# Led_Strip_5050_Parrallell.net
KiCad netlist of a schematic drawn in Altium Designer
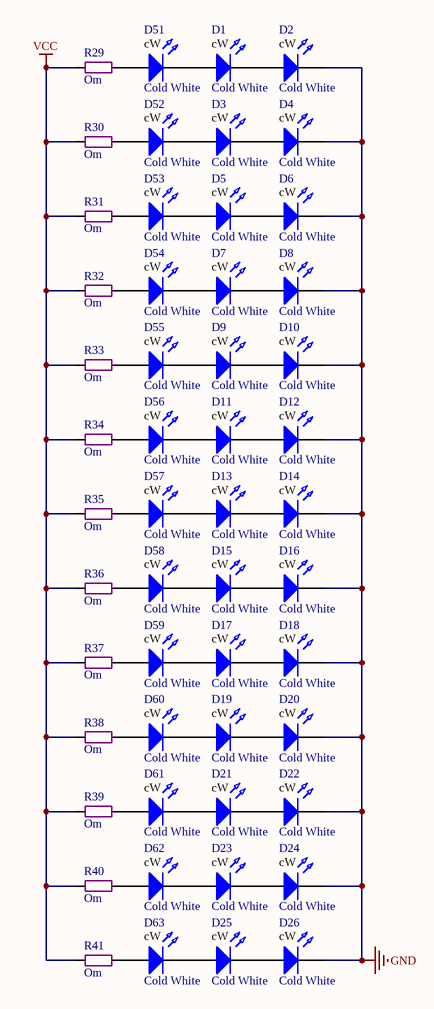
[diagram p0: Led Strip 5050 Parrallell.SchDoc]

(export (version "E")
  (design (tool "Eeschema 10.0.6"))
  (components
    (comp (ref "D1")
      (value "Cold White")
      (footprint "LED:LED SMD 5050 White compact Parrl")
      (description "?3v ?20mA")
      (libsource (lib "LED") (part "Led SMD White Cold"))
    )
    (comp (ref "D2")
      (value "Cold White")
      (footprint "LED:LED SMD 5050 White compact Parrl")
      (description "?3v ?20mA")
      (libsource (lib "LED") (part "Led SMD White Cold"))
    )
    (comp (ref "D3")
      (value "Cold White")
      (footprint "LED:LED SMD 5050 White compact Parrl")
      (description "?3v ?20mA")
      (libsource (lib "LED") (part "Led SMD White Cold"))
    )
    (comp (ref "D4")
      (value "Cold White")
      (footprint "LED:LED SMD 5050 White compact Parrl")
      (description "?3v ?20mA")
      (libsource (lib "LED") (part "Led SMD White Cold"))
    )
    (comp (ref "D5")
      (value "Cold White")
      (footprint "LED:LED SMD 5050 White compact Parrl")
      (description "?3v ?20mA")
      (libsource (lib "LED") (part "Led SMD White Cold"))
    )
    (comp (ref "D6")
      (value "Cold White")
      (footprint "LED:LED SMD 5050 White compact Parrl")
      (description "?3v ?20mA")
      (libsource (lib "LED") (part "Led SMD White Cold"))
    )
    (comp (ref "D7")
      (value "Cold White")
      (footprint "LED:LED SMD 5050 White compact Parrl")
      (description "?3v ?20mA")
      (libsource (lib "LED") (part "Led SMD White Cold"))
    )
    (comp (ref "D8")
      (value "Cold White")
      (footprint "LED:LED SMD 5050 White compact Parrl")
      (description "?3v ?20mA")
      (libsource (lib "LED") (part "Led SMD White Cold"))
    )
    (comp (ref "D9")
      (value "Cold White")
      (footprint "LED:LED SMD 5050 White compact Parrl")
      (description "?3v ?20mA")
      (libsource (lib "LED") (part "Led SMD White Cold"))
    )
    (comp (ref "D10")
      (value "Cold White")
      (footprint "LED:LED SMD 5050 White compact Parrl")
      (description "?3v ?20mA")
      (libsource (lib "LED") (part "Led SMD White Cold"))
    )
    (comp (ref "D11")
      (value "Cold White")
      (footprint "LED:LED SMD 5050 White compact Parrl")
      (description "?3v ?20mA")
      (libsource (lib "LED") (part "Led SMD White Cold"))
    )
    (comp (ref "D12")
      (value "Cold White")
      (footprint "LED:LED SMD 5050 White compact Parrl")
      (description "?3v ?20mA")
      (libsource (lib "LED") (part "Led SMD White Cold"))
    )
    (comp (ref "D13")
      (value "Cold White")
      (footprint "LED:LED SMD 5050 White compact Parrl")
      (description "?3v ?20mA")
      (libsource (lib "LED") (part "Led SMD White Cold"))
    )
    (comp (ref "D14")
      (value "Cold White")
      (footprint "LED:LED SMD 5050 White compact Parrl")
      (description "?3v ?20mA")
      (libsource (lib "LED") (part "Led SMD White Cold"))
    )
    (comp (ref "D15")
      (value "Cold White")
      (footprint "LED:LED SMD 5050 White compact Parrl")
      (description "?3v ?20mA")
      (libsource (lib "LED") (part "Led SMD White Cold"))
    )
    (comp (ref "D16")
      (value "Cold White")
      (footprint "LED:LED SMD 5050 White compact Parrl")
      (description "?3v ?20mA")
      (libsource (lib "LED") (part "Led SMD White Cold"))
    )
    (comp (ref "D17")
      (value "Cold White")
      (footprint "LED:LED SMD 5050 White compact Parrl")
      (description "?3v ?20mA")
      (libsource (lib "LED") (part "Led SMD White Cold"))
    )
    (comp (ref "D18")
      (value "Cold White")
      (footprint "LED:LED SMD 5050 White compact Parrl")
      (description "?3v ?20mA")
      (libsource (lib "LED") (part "Led SMD White Cold"))
    )
    (comp (ref "D19")
      (value "Cold White")
      (footprint "LED:LED SMD 5050 White compact Parrl")
      (description "?3v ?20mA")
      (libsource (lib "LED") (part "Led SMD White Cold"))
    )
    (comp (ref "D20")
      (value "Cold White")
      (footprint "LED:LED SMD 5050 White compact Parrl")
      (description "?3v ?20mA")
      (libsource (lib "LED") (part "Led SMD White Cold"))
    )
    (comp (ref "D21")
      (value "Cold White")
      (footprint "LED:LED SMD 5050 White compact Parrl")
      (description "?3v ?20mA")
      (libsource (lib "LED") (part "Led SMD White Cold"))
    )
    (comp (ref "D22")
      (value "Cold White")
      (footprint "LED:LED SMD 5050 White compact Parrl")
      (description "?3v ?20mA")
      (libsource (lib "LED") (part "Led SMD White Cold"))
    )
    (comp (ref "D23")
      (value "Cold White")
      (footprint "LED:LED SMD 5050 White compact Parrl")
      (description "?3v ?20mA")
      (libsource (lib "LED") (part "Led SMD White Cold"))
    )
    (comp (ref "D24")
      (value "Cold White")
      (footprint "LED:LED SMD 5050 White compact Parrl")
      (description "?3v ?20mA")
      (libsource (lib "LED") (part "Led SMD White Cold"))
    )
    (comp (ref "D25")
      (value "Cold White")
      (footprint "LED:LED SMD 5050 White compact Parrl")
      (description "?3v ?20mA")
      (libsource (lib "LED") (part "Led SMD White Cold"))
    )
    (comp (ref "D26")
      (value "Cold White")
      (footprint "LED:LED SMD 5050 White compact Parrl")
      (description "?3v ?20mA")
      (libsource (lib "LED") (part "Led SMD White Cold"))
    )
    (comp (ref "D51")
      (value "Cold White")
      (footprint "LED:LED SMD 5050 White compact Parrl")
      (description "?3v ?20mA")
      (libsource (lib "LED") (part "Led SMD White Cold"))
    )
    (comp (ref "D52")
      (value "Cold White")
      (footprint "LED:LED SMD 5050 White compact Parrl")
      (description "?3v ?20mA")
      (libsource (lib "LED") (part "Led SMD White Cold"))
    )
    (comp (ref "D53")
      (value "Cold White")
      (footprint "LED:LED SMD 5050 White compact Parrl")
      (description "?3v ?20mA")
      (libsource (lib "LED") (part "Led SMD White Cold"))
    )
    (comp (ref "D54")
      (value "Cold White")
      (footprint "LED:LED SMD 5050 White compact Parrl")
      (description "?3v ?20mA")
      (libsource (lib "LED") (part "Led SMD White Cold"))
    )
    (comp (ref "D55")
      (value "Cold White")
      (footprint "LED:LED SMD 5050 White compact Parrl")
      (description "?3v ?20mA")
      (libsource (lib "LED") (part "Led SMD White Cold"))
    )
    (comp (ref "D56")
      (value "Cold White")
      (footprint "LED:LED SMD 5050 White compact Parrl")
      (description "?3v ?20mA")
      (libsource (lib "LED") (part "Led SMD White Cold"))
    )
    (comp (ref "D57")
      (value "Cold White")
      (footprint "LED:LED SMD 5050 White compact Parrl")
      (description "?3v ?20mA")
      (libsource (lib "LED") (part "Led SMD White Cold"))
    )
    (comp (ref "D58")
      (value "Cold White")
      (footprint "LED:LED SMD 5050 White compact Parrl")
      (description "?3v ?20mA")
      (libsource (lib "LED") (part "Led SMD White Cold"))
    )
    (comp (ref "D59")
      (value "Cold White")
      (footprint "LED:LED SMD 5050 White compact Parrl")
      (description "?3v ?20mA")
      (libsource (lib "LED") (part "Led SMD White Cold"))
    )
    (comp (ref "D60")
      (value "Cold White")
      (footprint "LED:LED SMD 5050 White compact Parrl")
      (description "?3v ?20mA")
      (libsource (lib "LED") (part "Led SMD White Cold"))
    )
    (comp (ref "D61")
      (value "Cold White")
      (footprint "LED:LED SMD 5050 White compact Parrl")
      (description "?3v ?20mA")
      (libsource (lib "LED") (part "Led SMD White Cold"))
    )
    (comp (ref "D62")
      (value "Cold White")
      (footprint "LED:LED SMD 5050 White compact Parrl")
      (description "?3v ?20mA")
      (libsource (lib "LED") (part "Led SMD White Cold"))
    )
    (comp (ref "D63")
      (value "Cold White")
      (footprint "LED:LED SMD 5050 White compact Parrl")
      (description "?3v ?20mA")
      (libsource (lib "LED") (part "Led SMD White Cold"))
    )
    (comp (ref "R29")
      (value "Om")
      (footprint "PassiveComponents:SMD 1206 (3216)")
      (libsource (lib "PassiveComponents") (part "Res SMD 1206"))
    )
    (comp (ref "R30")
      (value "Om")
      (footprint "PassiveComponents:SMD 1206 (3216)")
      (libsource (lib "PassiveComponents") (part "Res SMD 1206"))
    )
    (comp (ref "R31")
      (value "Om")
      (footprint "PassiveComponents:SMD 1206 (3216)")
      (libsource (lib "PassiveComponents") (part "Res SMD 1206"))
    )
    (comp (ref "R32")
      (value "Om")
      (footprint "PassiveComponents:SMD 1206 (3216)")
      (libsource (lib "PassiveComponents") (part "Res SMD 1206"))
    )
    (comp (ref "R33")
      (value "Om")
      (footprint "PassiveComponents:SMD 1206 (3216)")
      (libsource (lib "PassiveComponents") (part "Res SMD 1206"))
    )
    (comp (ref "R34")
      (value "Om")
      (footprint "PassiveComponents:SMD 1206 (3216)")
      (libsource (lib "PassiveComponents") (part "Res SMD 1206"))
    )
    (comp (ref "R35")
      (value "Om")
      (footprint "PassiveComponents:SMD 1206 (3216)")
      (libsource (lib "PassiveComponents") (part "Res SMD 1206"))
    )
    (comp (ref "R36")
      (value "Om")
      (footprint "PassiveComponents:SMD 1206 (3216)")
      (libsource (lib "PassiveComponents") (part "Res SMD 1206"))
    )
    (comp (ref "R37")
      (value "Om")
      (footprint "PassiveComponents:SMD 1206 (3216)")
      (libsource (lib "PassiveComponents") (part "Res SMD 1206"))
    )
    (comp (ref "R38")
      (value "Om")
      (footprint "PassiveComponents:SMD 1206 (3216)")
      (libsource (lib "PassiveComponents") (part "Res SMD 1206"))
    )
    (comp (ref "R39")
      (value "Om")
      (footprint "PassiveComponents:SMD 1206 (3216)")
      (libsource (lib "PassiveComponents") (part "Res SMD 1206"))
    )
    (comp (ref "R40")
      (value "Om")
      (footprint "PassiveComponents:SMD 1206 (3216)")
      (libsource (lib "PassiveComponents") (part "Res SMD 1206"))
    )
    (comp (ref "R41")
      (value "Om")
      (footprint "PassiveComponents:SMD 1206 (3216)")
      (libsource (lib "PassiveComponents") (part "Res SMD 1206"))
    )
  )
  (nets
    (net (code "1") (name "GND") (class "Default")
      (node (ref "D10") (pin "K") (pinfunction "K_K") (pintype "passive"))
      (node (ref "D12") (pin "K") (pinfunction "K_K") (pintype "passive"))
      (node (ref "D14") (pin "K") (pinfunction "K_K") (pintype "passive"))
      (node (ref "D16") (pin "K") (pinfunction "K_K") (pintype "passive"))
      (node (ref "D18") (pin "K") (pinfunction "K_K") (pintype "passive"))
      (node (ref "D2") (pin "K") (pinfunction "K_K") (pintype "passive"))
      (node (ref "D20") (pin "K") (pinfunction "K_K") (pintype "passive"))
      (node (ref "D22") (pin "K") (pinfunction "K_K") (pintype "passive"))
      (node (ref "D24") (pin "K") (pinfunction "K_K") (pintype "passive"))
      (node (ref "D26") (pin "K") (pinfunction "K_K") (pintype "passive"))
      (node (ref "D4") (pin "K") (pinfunction "K_K") (pintype "passive"))
      (node (ref "D6") (pin "K") (pinfunction "K_K") (pintype "passive"))
      (node (ref "D8") (pin "K") (pinfunction "K_K") (pintype "passive"))
    )
    (net (code "2") (name "Net-(D1-PadA)") (class "Default")
      (node (ref "D1") (pin "A") (pinfunction "A_A") (pintype "passive"))
      (node (ref "D51") (pin "K") (pinfunction "K_K") (pintype "passive"))
    )
    (net (code "3") (name "Net-(D1-PadK)") (class "Default")
      (node (ref "D1") (pin "K") (pinfunction "K_K") (pintype "passive"))
      (node (ref "D2") (pin "A") (pinfunction "A_A") (pintype "passive"))
    )
    (net (code "4") (name "Net-(D3-PadA)") (class "Default")
      (node (ref "D3") (pin "A") (pinfunction "A_A") (pintype "passive"))
      (node (ref "D52") (pin "K") (pinfunction "K_K") (pintype "passive"))
    )
    (net (code "5") (name "Net-(D3-PadK)") (class "Default")
      (node (ref "D3") (pin "K") (pinfunction "K_K") (pintype "passive"))
      (node (ref "D4") (pin "A") (pinfunction "A_A") (pintype "passive"))
    )
    (net (code "6") (name "Net-(D5-PadA)") (class "Default")
      (node (ref "D5") (pin "A") (pinfunction "A_A") (pintype "passive"))
      (node (ref "D53") (pin "K") (pinfunction "K_K") (pintype "passive"))
    )
    (net (code "7") (name "Net-(D5-PadK)") (class "Default")
      (node (ref "D5") (pin "K") (pinfunction "K_K") (pintype "passive"))
      (node (ref "D6") (pin "A") (pinfunction "A_A") (pintype "passive"))
    )
    (net (code "8") (name "Net-(D7-PadK)") (class "Default")
      (node (ref "D7") (pin "K") (pinfunction "K_K") (pintype "passive"))
      (node (ref "D8") (pin "A") (pinfunction "A_A") (pintype "passive"))
    )
    (net (code "9") (name "Net-(D10-PadA)") (class "Default")
      (node (ref "D10") (pin "A") (pinfunction "A_A") (pintype "passive"))
      (node (ref "D9") (pin "K") (pinfunction "K_K") (pintype "passive"))
    )
    (net (code "10") (name "Net-(D11-PadA)") (class "Default")
      (node (ref "D11") (pin "A") (pinfunction "A_A") (pintype "passive"))
      (node (ref "D56") (pin "K") (pinfunction "K_K") (pintype "passive"))
    )
    (net (code "11") (name "Net-(D11-PadK)") (class "Default")
      (node (ref "D11") (pin "K") (pinfunction "K_K") (pintype "passive"))
      (node (ref "D12") (pin "A") (pinfunction "A_A") (pintype "passive"))
    )
    (net (code "12") (name "Net-(D13-PadA)") (class "Default")
      (node (ref "D13") (pin "A") (pinfunction "A_A") (pintype "passive"))
      (node (ref "D57") (pin "K") (pinfunction "K_K") (pintype "passive"))
    )
    (net (code "13") (name "Net-(D13-PadK)") (class "Default")
      (node (ref "D13") (pin "K") (pinfunction "K_K") (pintype "passive"))
      (node (ref "D14") (pin "A") (pinfunction "A_A") (pintype "passive"))
    )
    (net (code "14") (name "Net-(D15-PadA)") (class "Default")
      (node (ref "D15") (pin "A") (pinfunction "A_A") (pintype "passive"))
      (node (ref "D58") (pin "K") (pinfunction "K_K") (pintype "passive"))
    )
    (net (code "15") (name "Net-(D15-PadK)") (class "Default")
      (node (ref "D15") (pin "K") (pinfunction "K_K") (pintype "passive"))
      (node (ref "D16") (pin "A") (pinfunction "A_A") (pintype "passive"))
    )
    (net (code "16") (name "Net-(D17-PadA)") (class "Default")
      (node (ref "D17") (pin "A") (pinfunction "A_A") (pintype "passive"))
      (node (ref "D59") (pin "K") (pinfunction "K_K") (pintype "passive"))
    )
    (net (code "17") (name "Net-(D17-PadK)") (class "Default")
      (node (ref "D17") (pin "K") (pinfunction "K_K") (pintype "passive"))
      (node (ref "D18") (pin "A") (pinfunction "A_A") (pintype "passive"))
    )
    (net (code "18") (name "Net-(D19-PadA)") (class "Default")
      (node (ref "D19") (pin "A") (pinfunction "A_A") (pintype "passive"))
      (node (ref "D60") (pin "K") (pinfunction "K_K") (pintype "passive"))
    )
    (net (code "19") (name "Net-(D19-PadK)") (class "Default")
      (node (ref "D19") (pin "K") (pinfunction "K_K") (pintype "passive"))
      (node (ref "D20") (pin "A") (pinfunction "A_A") (pintype "passive"))
    )
    (net (code "20") (name "Net-(D21-PadA)") (class "Default")
      (node (ref "D21") (pin "A") (pinfunction "A_A") (pintype "passive"))
      (node (ref "D61") (pin "K") (pinfunction "K_K") (pintype "passive"))
    )
    (net (code "21") (name "Net-(D21-PadK)") (class "Default")
      (node (ref "D21") (pin "K") (pinfunction "K_K") (pintype "passive"))
      (node (ref "D22") (pin "A") (pinfunction "A_A") (pintype "passive"))
    )
    (net (code "22") (name "Net-(D23-PadA)") (class "Default")
      (node (ref "D23") (pin "A") (pinfunction "A_A") (pintype "passive"))
      (node (ref "D62") (pin "K") (pinfunction "K_K") (pintype "passive"))
    )
    (net (code "23") (name "Net-(D23-PadK)") (class "Default")
      (node (ref "D23") (pin "K") (pinfunction "K_K") (pintype "passive"))
      (node (ref "D24") (pin "A") (pinfunction "A_A") (pintype "passive"))
    )
    (net (code "24") (name "Net-(D25-PadA)") (class "Default")
      (node (ref "D25") (pin "A") (pinfunction "A_A") (pintype "passive"))
      (node (ref "D63") (pin "K") (pinfunction "K_K") (pintype "passive"))
    )
    (net (code "25") (name "Net-(D25-PadK)") (class "Default")
      (node (ref "D25") (pin "K") (pinfunction "K_K") (pintype "passive"))
      (node (ref "D26") (pin "A") (pinfunction "A_A") (pintype "passive"))
    )
    (net (code "26") (name "Net-(D51-PadA)") (class "Default")
      (node (ref "D51") (pin "A") (pinfunction "A_A") (pintype "passive"))
      (node (ref "R29") (pin "2") (pinfunction "2_2") (pintype "passive"))
    )
    (net (code "27") (name "Net-(D52-PadA)") (class "Default")
      (node (ref "D52") (pin "A") (pinfunction "A_A") (pintype "passive"))
      (node (ref "R30") (pin "2") (pinfunction "2_2") (pintype "passive"))
    )
    (net (code "28") (name "Net-(D53-PadA)") (class "Default")
      (node (ref "D53") (pin "A") (pinfunction "A_A") (pintype "passive"))
      (node (ref "R31") (pin "2") (pinfunction "2_2") (pintype "passive"))
    )
    (net (code "29") (name "Net-(D54-PadA)") (class "Default")
      (node (ref "D54") (pin "A") (pinfunction "A_A") (pintype "passive"))
      (node (ref "R32") (pin "2") (pinfunction "2_2") (pintype "passive"))
    )
    (net (code "30") (name "Net-(D54-PadK)") (class "Default")
      (node (ref "D54") (pin "K") (pinfunction "K_K") (pintype "passive"))
      (node (ref "D7") (pin "A") (pinfunction "A_A") (pintype "passive"))
    )
    (net (code "31") (name "Net-(D55-PadA)") (class "Default")
      (node (ref "D55") (pin "A") (pinfunction "A_A") (pintype "passive"))
      (node (ref "R33") (pin "2") (pinfunction "2_2") (pintype "passive"))
    )
    (net (code "32") (name "Net-(D55-PadK)") (class "Default")
      (node (ref "D55") (pin "K") (pinfunction "K_K") (pintype "passive"))
      (node (ref "D9") (pin "A") (pinfunction "A_A") (pintype "passive"))
    )
    (net (code "33") (name "Net-(D56-PadA)") (class "Default")
      (node (ref "D56") (pin "A") (pinfunction "A_A") (pintype "passive"))
      (node (ref "R34") (pin "2") (pinfunction "2_2") (pintype "passive"))
    )
    (net (code "34") (name "Net-(D57-PadA)") (class "Default")
      (node (ref "D57") (pin "A") (pinfunction "A_A") (pintype "passive"))
      (node (ref "R35") (pin "2") (pinfunction "2_2") (pintype "passive"))
    )
    (net (code "35") (name "Net-(D58-PadA)") (class "Default")
      (node (ref "D58") (pin "A") (pinfunction "A_A") (pintype "passive"))
      (node (ref "R36") (pin "2") (pinfunction "2_2") (pintype "passive"))
    )
    (net (code "36") (name "Net-(D59-PadA)") (class "Default")
      (node (ref "D59") (pin "A") (pinfunction "A_A") (pintype "passive"))
      (node (ref "R37") (pin "2") (pinfunction "2_2") (pintype "passive"))
    )
    (net (code "37") (name "Net-(D60-PadA)") (class "Default")
      (node (ref "D60") (pin "A") (pinfunction "A_A") (pintype "passive"))
      (node (ref "R38") (pin "2") (pinfunction "2_2") (pintype "passive"))
    )
    (net (code "38") (name "Net-(D61-PadA)") (class "Default")
      (node (ref "D61") (pin "A") (pinfunction "A_A") (pintype "passive"))
      (node (ref "R39") (pin "2") (pinfunction "2_2") (pintype "passive"))
    )
    (net (code "39") (name "Net-(D62-PadA)") (class "Default")
      (node (ref "D62") (pin "A") (pinfunction "A_A") (pintype "passive"))
      (node (ref "R40") (pin "2") (pinfunction "2_2") (pintype "passive"))
    )
    (net (code "40") (name "Net-(D63-PadA)") (class "Default")
      (node (ref "D63") (pin "A") (pinfunction "A_A") (pintype "passive"))
      (node (ref "R41") (pin "2") (pinfunction "2_2") (pintype "passive"))
    )
    (net (code "41") (name "VCC") (class "Default")
      (node (ref "R29") (pin "1") (pinfunction "1_1") (pintype "passive"))
      (node (ref "R30") (pin "1") (pinfunction "1_1") (pintype "passive"))
      (node (ref "R31") (pin "1") (pinfunction "1_1") (pintype "passive"))
      (node (ref "R32") (pin "1") (pinfunction "1_1") (pintype "passive"))
      (node (ref "R33") (pin "1") (pinfunction "1_1") (pintype "passive"))
      (node (ref "R34") (pin "1") (pinfunction "1_1") (pintype "passive"))
      (node (ref "R35") (pin "1") (pinfunction "1_1") (pintype "passive"))
      (node (ref "R36") (pin "1") (pinfunction "1_1") (pintype "passive"))
      (node (ref "R37") (pin "1") (pinfunction "1_1") (pintype "passive"))
      (node (ref "R38") (pin "1") (pinfunction "1_1") (pintype "passive"))
      (node (ref "R39") (pin "1") (pinfunction "1_1") (pintype "passive"))
      (node (ref "R40") (pin "1") (pinfunction "1_1") (pintype "passive"))
      (node (ref "R41") (pin "1") (pinfunction "1_1") (pintype "passive"))
    )
  )
)
